# sboxs.net
KiCad netlist of a schematic drawn in EAGLE
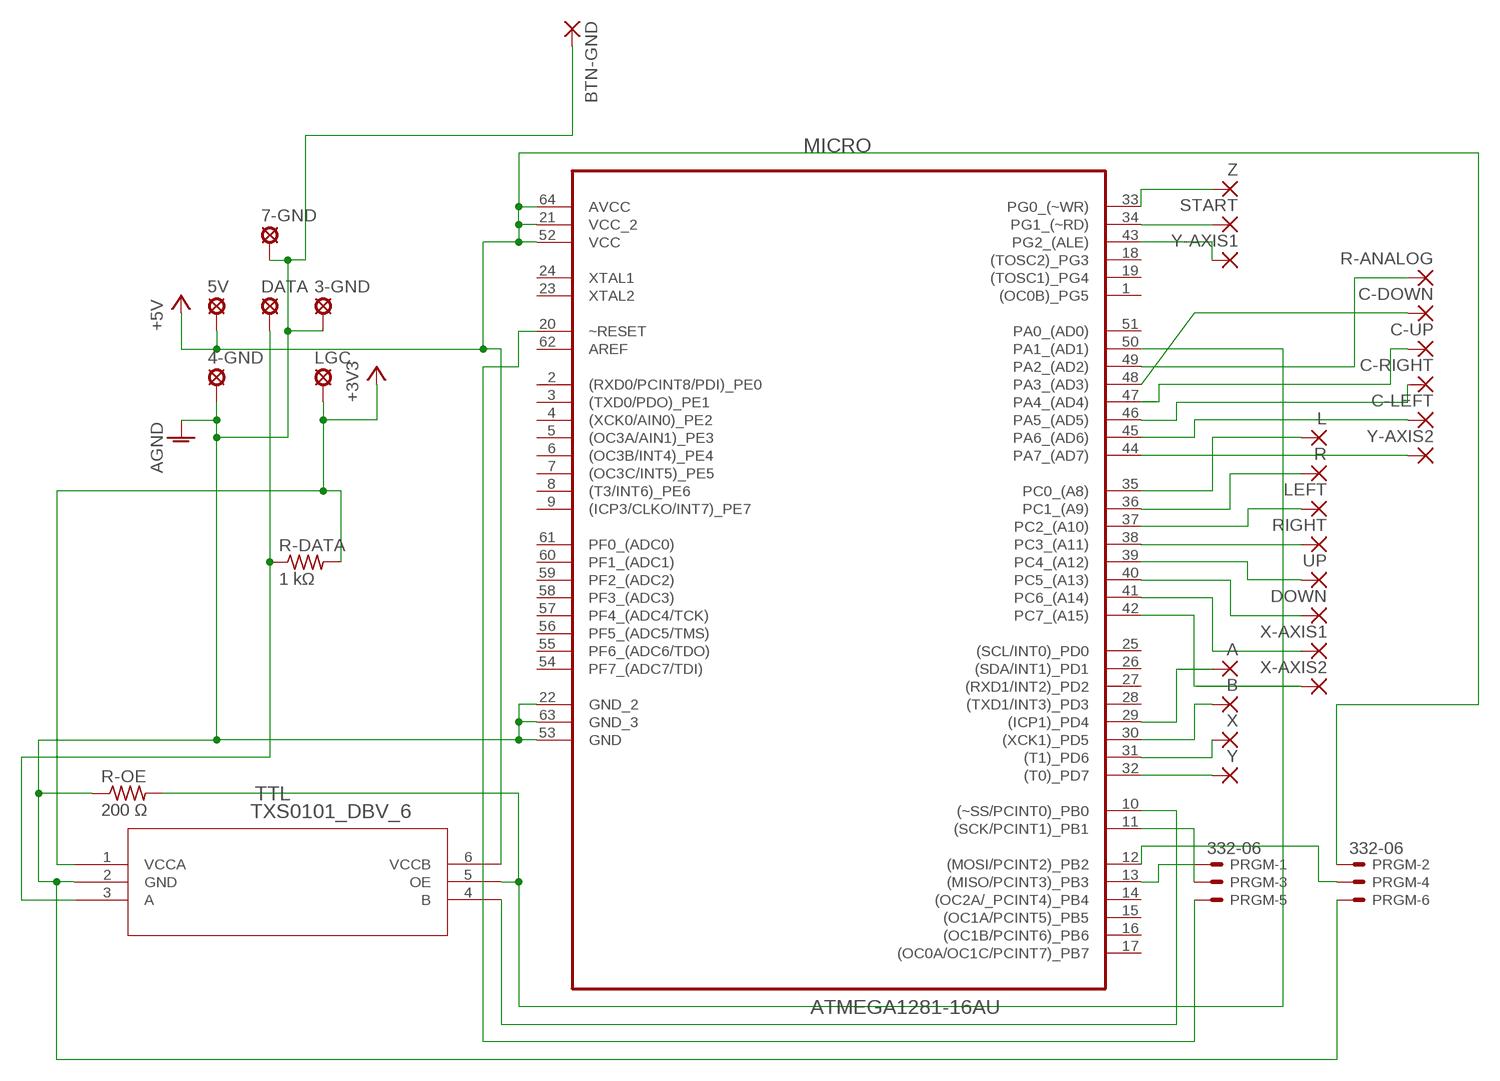
[diagram p0: schematic, sheet 1]

(export (version "E")
  (design (tool "Eeschema 10.0.6"))
  (components
    (comp (ref "3-GND")
      (value "LSP10")
      (footprint "eagle-import:LSP10")
      (libsource (lib "eagle-import") (part "LSP10"))
    )
    (comp (ref "4-GND")
      (value "LSP10")
      (footprint "eagle-import:LSP10")
      (libsource (lib "eagle-import") (part "LSP10"))
    )
    (comp (ref "5V")
      (value "LSP10")
      (footprint "eagle-import:LSP10")
      (libsource (lib "eagle-import") (part "LSP10"))
    )
    (comp (ref "7-GND")
      (value "LSP10")
      (footprint "eagle-import:LSP10")
      (libsource (lib "eagle-import") (part "LSP10"))
    )
    (comp (ref "A")
      (value "1,6/0,8")
      (footprint "eagle-import:1,6_0,8")
      (libsource (lib "eagle-import") (part "1,6/0,8"))
    )
    (comp (ref "B")
      (value "1,6/0,8")
      (footprint "eagle-import:1,6_0,8")
      (libsource (lib "eagle-import") (part "1,6/0,8"))
    )
    (comp (ref "BTN-GND")
      (value "1,6/0,8")
      (footprint "eagle-import:1,6_0,8")
      (libsource (lib "eagle-import") (part "1,6/0,8"))
    )
    (comp (ref "C-DOWN")
      (value "1,6/0,8")
      (footprint "eagle-import:1,6_0,8")
      (libsource (lib "eagle-import") (part "1,6/0,8"))
    )
    (comp (ref "C-LEFT")
      (value "1,6/0,8")
      (footprint "eagle-import:1,6_0,8")
      (libsource (lib "eagle-import") (part "1,6/0,8"))
    )
    (comp (ref "C-RIGHT")
      (value "1,6/0,8")
      (footprint "eagle-import:1,6_0,8")
      (libsource (lib "eagle-import") (part "1,6/0,8"))
    )
    (comp (ref "C-UP")
      (value "1,6/0,8")
      (footprint "eagle-import:1,6_0,8")
      (libsource (lib "eagle-import") (part "1,6/0,8"))
    )
    (comp (ref "DATA")
      (value "LSP10")
      (footprint "eagle-import:LSP10")
      (libsource (lib "eagle-import") (part "LSP10"))
    )
    (comp (ref "DOWN")
      (value "1,6/0,8")
      (footprint "eagle-import:1,6_0,8")
      (libsource (lib "eagle-import") (part "1,6/0,8"))
    )
    (comp (ref "L")
      (value "1,6/0,8")
      (footprint "eagle-import:1,6_0,8")
      (libsource (lib "eagle-import") (part "1,6/0,8"))
    )
    (comp (ref "LEFT")
      (value "1,6/0,8")
      (footprint "eagle-import:1,6_0,8")
      (libsource (lib "eagle-import") (part "1,6/0,8"))
    )
    (comp (ref "LGC")
      (value "LSP10")
      (footprint "eagle-import:LSP10")
      (libsource (lib "eagle-import") (part "LSP10"))
    )
    (comp (ref "MICRO")
      (value "ATMEGA1281-16AU")
      (footprint "eagle-import:QFP80P1600X1600X120-64N")
      (libsource (lib "eagle-import") (part "ATMEGA1281-16AU"))
    )
    (comp (ref "PRGM")
      (value "332-06")
      (footprint "eagle-import:332-06")
      (libsource (lib "eagle-import") (part "332-06"))
    )
    (comp (ref "R")
      (value "1,6/0,8")
      (footprint "eagle-import:1,6_0,8")
      (libsource (lib "eagle-import") (part "1,6/0,8"))
    )
    (comp (ref "R-ANALOG")
      (value "1,6/0,8")
      (footprint "eagle-import:1,6_0,8")
      (libsource (lib "eagle-import") (part "1,6/0,8"))
    )
    (comp (ref "R-DATA")
      (value "1 kΩ")
      (footprint "eagle-import:0207_12")
      (libsource (lib "eagle-import") (part "R-US_0207/12"))
    )
    (comp (ref "R-OE")
      (value "200 Ω")
      (footprint "eagle-import:0207_12")
      (libsource (lib "eagle-import") (part "R-US_0207/12"))
    )
    (comp (ref "RIGHT")
      (value "1,6/0,8")
      (footprint "eagle-import:1,6_0,8")
      (libsource (lib "eagle-import") (part "1,6/0,8"))
    )
    (comp (ref "START")
      (value "1,6/0,8")
      (footprint "eagle-import:1,6_0,8")
      (libsource (lib "eagle-import") (part "1,6/0,8"))
    )
    (comp (ref "TTL")
      (value "TXS0101_DBV_6")
      (footprint "eagle-import:DBV6")
      (fields
        (field (name "GENERIC_PART_NUMBER") "TXS0101")
        (field (name "MANUFACTURER") "Texas Instruments")
        (field (name "MANUFACTURER_PART_NUMBER") "txs0101_dbv_6")
      )
      (libsource (lib "eagle-import") (part "TXS0101_DBV_6"))
    )
    (comp (ref "UP")
      (value "1,6/0,8")
      (footprint "eagle-import:1,6_0,8")
      (libsource (lib "eagle-import") (part "1,6/0,8"))
    )
    (comp (ref "X")
      (value "1,6/0,8")
      (footprint "eagle-import:1,6_0,8")
      (libsource (lib "eagle-import") (part "1,6/0,8"))
    )
    (comp (ref "X-AXIS1")
      (value "1,6/0,8")
      (footprint "eagle-import:1,6_0,8")
      (libsource (lib "eagle-import") (part "1,6/0,8"))
    )
    (comp (ref "X-AXIS2")
      (value "1,6/0,8")
      (footprint "eagle-import:1,6_0,8")
      (libsource (lib "eagle-import") (part "1,6/0,8"))
    )
    (comp (ref "Y")
      (value "1,6/0,8")
      (footprint "eagle-import:1,6_0,8")
      (libsource (lib "eagle-import") (part "1,6/0,8"))
    )
    (comp (ref "Y-AXIS1")
      (value "1,6/0,8")
      (footprint "eagle-import:1,6_0,8")
      (libsource (lib "eagle-import") (part "1,6/0,8"))
    )
    (comp (ref "Y-AXIS2")
      (value "1,6/0,8")
      (footprint "eagle-import:1,6_0,8")
      (libsource (lib "eagle-import") (part "1,6/0,8"))
    )
    (comp (ref "Z")
      (value "1,6/0,8")
      (footprint "eagle-import:1,6_0,8")
      (libsource (lib "eagle-import") (part "1,6/0,8"))
    )
  )
  (nets
    (net (code "1") (name "+3V3") (class "Default")
      (node (ref "LGC") (pin "MP") (pinfunction "MP_MP") (pintype "passive"))
      (node (ref "R-DATA") (pin "2") (pinfunction "2_2") (pintype "passive"))
      (node (ref "TTL") (pin "1") (pinfunction "VCCA_1") (pintype "power_in"))
    )
    (net (code "2") (name "+5V") (class "Default")
      (node (ref "5V") (pin "MP") (pinfunction "MP_MP") (pintype "passive"))
      (node (ref "MICRO") (pin "21") (pinfunction "VCC_2_21") (pintype "power_in"))
      (node (ref "MICRO") (pin "52") (pinfunction "VCC_52") (pintype "power_in"))
      (node (ref "MICRO") (pin "64") (pinfunction "AVCC_64") (pintype "power_in"))
      (node (ref "PRGM") (pin "2") (pinfunction "S_2") (pintype "passive"))
      (node (ref "TTL") (pin "6") (pinfunction "VCCB_6") (pintype "power_in"))
    )
    (net (code "3") (name "AGND") (class "Default")
      (node (ref "3-GND") (pin "MP") (pinfunction "MP_MP") (pintype "passive"))
      (node (ref "4-GND") (pin "MP") (pinfunction "MP_MP") (pintype "passive"))
      (node (ref "7-GND") (pin "MP") (pinfunction "MP_MP") (pintype "passive"))
      (node (ref "BTN-GND") (pin "1") (pinfunction "P_1") (pintype "passive"))
      (node (ref "MICRO") (pin "22") (pinfunction "GND_2_22") (pintype "passive"))
      (node (ref "MICRO") (pin "53") (pinfunction "GND_53") (pintype "passive"))
      (node (ref "MICRO") (pin "63") (pinfunction "GND_3_63") (pintype "passive"))
      (node (ref "PRGM") (pin "6") (pinfunction "S_6") (pintype "passive"))
      (node (ref "R-OE") (pin "1") (pinfunction "1_1") (pintype "passive"))
      (node (ref "TTL") (pin "2") (pinfunction "GND_2") (pintype "power_in"))
    )
    (net (code "4") (name "Net-(A-P)") (class "Default")
      (node (ref "A") (pin "1") (pinfunction "P_1") (pintype "passive"))
      (node (ref "MICRO") (pin "29") (pinfunction "(ICP1)_PD4_29") (pintype "bidirectional"))
    )
    (net (code "5") (name "Net-(B-P)") (class "Default")
      (node (ref "B") (pin "1") (pinfunction "P_1") (pintype "passive"))
      (node (ref "MICRO") (pin "30") (pinfunction "(XCK1)_PD5_30") (pintype "bidirectional"))
    )
    (net (code "6") (name "Net-(C-DOWN-P)") (class "Default")
      (node (ref "C-DOWN") (pin "1") (pinfunction "P_1") (pintype "passive"))
      (node (ref "MICRO") (pin "48") (pinfunction "PA3_(AD3)_48") (pintype "bidirectional"))
    )
    (net (code "7") (name "Net-(C-LEFT-P)") (class "Default")
      (node (ref "C-LEFT") (pin "1") (pinfunction "P_1") (pintype "passive"))
      (node (ref "MICRO") (pin "45") (pinfunction "PA6_(AD6)_45") (pintype "bidirectional"))
    )
    (net (code "8") (name "Net-(C-RIGHT-P)") (class "Default")
      (node (ref "C-RIGHT") (pin "1") (pinfunction "P_1") (pintype "passive"))
      (node (ref "MICRO") (pin "46") (pinfunction "PA5_(AD5)_46") (pintype "bidirectional"))
    )
    (net (code "9") (name "Net-(C-UP-P)") (class "Default")
      (node (ref "C-UP") (pin "1") (pinfunction "P_1") (pintype "passive"))
      (node (ref "MICRO") (pin "47") (pinfunction "PA4_(AD4)_47") (pintype "bidirectional"))
    )
    (net (code "10") (name "Net-(DOWN-P)") (class "Default")
      (node (ref "DOWN") (pin "1") (pinfunction "P_1") (pintype "passive"))
      (node (ref "MICRO") (pin "40") (pinfunction "PC5_(A13)_40") (pintype "bidirectional"))
    )
    (net (code "11") (name "Net-(L-P)") (class "Default")
      (node (ref "L") (pin "1") (pinfunction "P_1") (pintype "passive"))
      (node (ref "MICRO") (pin "35") (pinfunction "PC0_(A8)_35") (pintype "bidirectional"))
    )
    (net (code "12") (name "Net-(LEFT-P)") (class "Default")
      (node (ref "LEFT") (pin "1") (pinfunction "P_1") (pintype "passive"))
      (node (ref "MICRO") (pin "37") (pinfunction "PC2_(A10)_37") (pintype "bidirectional"))
    )
    (net (code "13") (name "Net-(MICRO-(MISO{slash}PCINT3)_PB3)") (class "Default")
      (node (ref "MICRO") (pin "13") (pinfunction "(MISO/PCINT3)_PB3_13") (pintype "bidirectional"))
      (node (ref "PRGM") (pin "1") (pinfunction "S_1") (pintype "passive"))
    )
    (net (code "14") (name "Net-(MICRO-(MOSI{slash}PCINT2)_PB2)") (class "Default")
      (node (ref "MICRO") (pin "12") (pinfunction "(MOSI/PCINT2)_PB2_12") (pintype "bidirectional"))
      (node (ref "PRGM") (pin "4") (pinfunction "S_4") (pintype "passive"))
    )
    (net (code "15") (name "Net-(MICRO-(SCK{slash}PCINT1)_PB1)") (class "Default")
      (node (ref "MICRO") (pin "11") (pinfunction "(SCK/PCINT1)_PB1_11") (pintype "bidirectional"))
      (node (ref "PRGM") (pin "3") (pinfunction "S_3") (pintype "passive"))
    )
    (net (code "16") (name "Net-(MICRO-(T0)_PD7)") (class "Default")
      (node (ref "MICRO") (pin "32") (pinfunction "(T0)_PD7_32") (pintype "bidirectional"))
      (node (ref "Y") (pin "1") (pinfunction "P_1") (pintype "passive"))
    )
    (net (code "17") (name "Net-(MICRO-(T1)_PD6)") (class "Default")
      (node (ref "MICRO") (pin "31") (pinfunction "(T1)_PD6_31") (pintype "bidirectional"))
      (node (ref "X") (pin "1") (pinfunction "P_1") (pintype "passive"))
    )
    (net (code "18") (name "Net-(MICRO-(~{SS{slash}PCINT0})_PB0)") (class "Default")
      (node (ref "MICRO") (pin "10") (pinfunction "(~{SS/PCINT0})_PB0_10") (pintype "bidirectional"))
      (node (ref "TTL") (pin "4") (pinfunction "B_4") (pintype "bidirectional"))
    )
    (net (code "19") (name "Net-(MICRO-PA1_(AD1))") (class "Default")
      (node (ref "MICRO") (pin "50") (pinfunction "PA1_(AD1)_50") (pintype "bidirectional"))
      (node (ref "R-OE") (pin "2") (pinfunction "2_2") (pintype "passive"))
      (node (ref "TTL") (pin "5") (pinfunction "OE_5") (pintype "output"))
    )
    (net (code "20") (name "Net-(MICRO-PA2_(AD2))") (class "Default")
      (node (ref "MICRO") (pin "49") (pinfunction "PA2_(AD2)_49") (pintype "bidirectional"))
      (node (ref "R-ANALOG") (pin "1") (pinfunction "P_1") (pintype "passive"))
    )
    (net (code "21") (name "Net-(MICRO-PA7_(AD7))") (class "Default")
      (node (ref "MICRO") (pin "44") (pinfunction "PA7_(AD7)_44") (pintype "bidirectional"))
      (node (ref "Y-AXIS2") (pin "1") (pinfunction "P_1") (pintype "passive"))
    )
    (net (code "22") (name "Net-(MICRO-PC1_(A9))") (class "Default")
      (node (ref "MICRO") (pin "36") (pinfunction "PC1_(A9)_36") (pintype "bidirectional"))
      (node (ref "R") (pin "1") (pinfunction "P_1") (pintype "passive"))
    )
    (net (code "23") (name "Net-(MICRO-PC3_(A11))") (class "Default")
      (node (ref "MICRO") (pin "38") (pinfunction "PC3_(A11)_38") (pintype "bidirectional"))
      (node (ref "RIGHT") (pin "1") (pinfunction "P_1") (pintype "passive"))
    )
    (net (code "24") (name "Net-(MICRO-PC4_(A12))") (class "Default")
      (node (ref "MICRO") (pin "39") (pinfunction "PC4_(A12)_39") (pintype "bidirectional"))
      (node (ref "UP") (pin "1") (pinfunction "P_1") (pintype "passive"))
    )
    (net (code "25") (name "Net-(MICRO-PC6_(A14))") (class "Default")
      (node (ref "MICRO") (pin "41") (pinfunction "PC6_(A14)_41") (pintype "bidirectional"))
      (node (ref "X-AXIS1") (pin "1") (pinfunction "P_1") (pintype "passive"))
    )
    (net (code "26") (name "Net-(MICRO-PC7_(A15))") (class "Default")
      (node (ref "MICRO") (pin "42") (pinfunction "PC7_(A15)_42") (pintype "bidirectional"))
      (node (ref "X-AXIS2") (pin "1") (pinfunction "P_1") (pintype "passive"))
    )
    (net (code "27") (name "Net-(MICRO-PG0_(~{WR}))") (class "Default")
      (node (ref "MICRO") (pin "33") (pinfunction "PG0_(~{WR})_33") (pintype "bidirectional"))
      (node (ref "Z") (pin "1") (pinfunction "P_1") (pintype "passive"))
    )
    (net (code "28") (name "Net-(MICRO-PG1_(~{RD}))") (class "Default")
      (node (ref "MICRO") (pin "34") (pinfunction "PG1_(~{RD})_34") (pintype "bidirectional"))
      (node (ref "START") (pin "1") (pinfunction "P_1") (pintype "passive"))
    )
    (net (code "29") (name "Net-(MICRO-PG2_(ALE))") (class "Default")
      (node (ref "MICRO") (pin "43") (pinfunction "PG2_(ALE)_43") (pintype "bidirectional"))
      (node (ref "Y-AXIS1") (pin "1") (pinfunction "P_1") (pintype "passive"))
    )
    (net (code "30") (name "Net-(MICRO-~{RESET})") (class "Default")
      (node (ref "MICRO") (pin "20") (pinfunction "~{RESET}_20") (pintype "input"))
      (node (ref "PRGM") (pin "5") (pinfunction "S_5") (pintype "passive"))
    )
    (net (code "31") (name "Net-(TTL-A)") (class "Default")
      (node (ref "DATA") (pin "MP") (pinfunction "MP_MP") (pintype "passive"))
      (node (ref "R-DATA") (pin "1") (pinfunction "1_1") (pintype "passive"))
      (node (ref "TTL") (pin "3") (pinfunction "A_3") (pintype "bidirectional"))
    )
    (net (code "32") (name "unconnected-(MICRO-(ICP3{slash}CLKO{slash}INT7)_PE7-Pad9)") (class "Default")
      (node (ref "MICRO") (pin "9") (pinfunction "(ICP3/CLKO/INT7)_PE7_9") (pintype "bidirectional"))
    )
    (net (code "33") (name "unconnected-(MICRO-(OC0A{slash}OC1C{slash}PCINT7)_PB7-Pad17)") (class "Default")
      (node (ref "MICRO") (pin "17") (pinfunction "(OC0A/OC1C/PCINT7)_PB7_17") (pintype "bidirectional"))
    )
    (net (code "34") (name "unconnected-(MICRO-(OC0B)_PG5-Pad1)") (class "Default")
      (node (ref "MICRO") (pin "1") (pinfunction "(OC0B)_PG5_1") (pintype "bidirectional"))
    )
    (net (code "35") (name "unconnected-(MICRO-(OC1A{slash}PCINT5)_PB5-Pad15)") (class "Default")
      (node (ref "MICRO") (pin "15") (pinfunction "(OC1A/PCINT5)_PB5_15") (pintype "bidirectional"))
    )
    (net (code "36") (name "unconnected-(MICRO-(OC1B{slash}PCINT6)_PB6-Pad16)") (class "Default")
      (node (ref "MICRO") (pin "16") (pinfunction "(OC1B/PCINT6)_PB6_16") (pintype "bidirectional"))
    )
    (net (code "37") (name "unconnected-(MICRO-(OC2A{slash}_PCINT4)_PB4-Pad14)") (class "Default")
      (node (ref "MICRO") (pin "14") (pinfunction "(OC2A/_PCINT4)_PB4_14") (pintype "bidirectional"))
    )
    (net (code "38") (name "unconnected-(MICRO-(OC3A{slash}AIN1)_PE3-Pad5)") (class "Default")
      (node (ref "MICRO") (pin "5") (pinfunction "(OC3A/AIN1)_PE3_5") (pintype "bidirectional"))
    )
    (net (code "39") (name "unconnected-(MICRO-(OC3B{slash}INT4)_PE4-Pad6)") (class "Default")
      (node (ref "MICRO") (pin "6") (pinfunction "(OC3B/INT4)_PE4_6") (pintype "bidirectional"))
    )
    (net (code "40") (name "unconnected-(MICRO-(OC3C{slash}INT5)_PE5-Pad7)") (class "Default")
      (node (ref "MICRO") (pin "7") (pinfunction "(OC3C/INT5)_PE5_7") (pintype "bidirectional"))
    )
    (net (code "41") (name "unconnected-(MICRO-(RXD0{slash}PCINT8{slash}PDI)_PE0-Pad2)") (class "Default")
      (node (ref "MICRO") (pin "2") (pinfunction "(RXD0/PCINT8/PDI)_PE0_2") (pintype "bidirectional"))
    )
    (net (code "42") (name "unconnected-(MICRO-(RXD1{slash}INT2)_PD2-Pad27)") (class "Default")
      (node (ref "MICRO") (pin "27") (pinfunction "(RXD1/INT2)_PD2_27") (pintype "bidirectional"))
    )
    (net (code "43") (name "unconnected-(MICRO-(SCL{slash}INT0)_PD0-Pad25)") (class "Default")
      (node (ref "MICRO") (pin "25") (pinfunction "(SCL/INT0)_PD0_25") (pintype "bidirectional"))
    )
    (net (code "44") (name "unconnected-(MICRO-(SDA{slash}INT1)_PD1-Pad26)") (class "Default")
      (node (ref "MICRO") (pin "26") (pinfunction "(SDA/INT1)_PD1_26") (pintype "bidirectional"))
    )
    (net (code "45") (name "unconnected-(MICRO-(T3{slash}INT6)_PE6-Pad8)") (class "Default")
      (node (ref "MICRO") (pin "8") (pinfunction "(T3/INT6)_PE6_8") (pintype "bidirectional"))
    )
    (net (code "46") (name "unconnected-(MICRO-(TOSC1)_PG4-Pad19)") (class "Default")
      (node (ref "MICRO") (pin "19") (pinfunction "(TOSC1)_PG4_19") (pintype "bidirectional"))
    )
    (net (code "47") (name "unconnected-(MICRO-(TOSC2)_PG3-Pad18)") (class "Default")
      (node (ref "MICRO") (pin "18") (pinfunction "(TOSC2)_PG3_18") (pintype "bidirectional"))
    )
    (net (code "48") (name "unconnected-(MICRO-(TXD0{slash}PDO)_PE1-Pad3)") (class "Default")
      (node (ref "MICRO") (pin "3") (pinfunction "(TXD0/PDO)_PE1_3") (pintype "bidirectional"))
    )
    (net (code "49") (name "unconnected-(MICRO-(TXD1{slash}INT3)_PD3-Pad28)") (class "Default")
      (node (ref "MICRO") (pin "28") (pinfunction "(TXD1/INT3)_PD3_28") (pintype "bidirectional"))
    )
    (net (code "50") (name "unconnected-(MICRO-(XCK0{slash}AIN0)_PE2-Pad4)") (class "Default")
      (node (ref "MICRO") (pin "4") (pinfunction "(XCK0/AIN0)_PE2_4") (pintype "bidirectional"))
    )
    (net (code "51") (name "unconnected-(MICRO-AREF-Pad62)") (class "Default")
      (node (ref "MICRO") (pin "62") (pinfunction "AREF_62") (pintype "input"))
    )
    (net (code "52") (name "unconnected-(MICRO-PA0_(AD0)-Pad51)") (class "Default")
      (node (ref "MICRO") (pin "51") (pinfunction "PA0_(AD0)_51") (pintype "bidirectional"))
    )
    (net (code "53") (name "unconnected-(MICRO-PF0_(ADC0)-Pad61)") (class "Default")
      (node (ref "MICRO") (pin "61") (pinfunction "PF0_(ADC0)_61") (pintype "bidirectional"))
    )
    (net (code "54") (name "unconnected-(MICRO-PF1_(ADC1)-Pad60)") (class "Default")
      (node (ref "MICRO") (pin "60") (pinfunction "PF1_(ADC1)_60") (pintype "bidirectional"))
    )
    (net (code "55") (name "unconnected-(MICRO-PF2_(ADC2)-Pad59)") (class "Default")
      (node (ref "MICRO") (pin "59") (pinfunction "PF2_(ADC2)_59") (pintype "bidirectional"))
    )
    (net (code "56") (name "unconnected-(MICRO-PF3_(ADC3)-Pad58)") (class "Default")
      (node (ref "MICRO") (pin "58") (pinfunction "PF3_(ADC3)_58") (pintype "bidirectional"))
    )
    (net (code "57") (name "unconnected-(MICRO-PF4_(ADC4{slash}TCK)-Pad57)") (class "Default")
      (node (ref "MICRO") (pin "57") (pinfunction "PF4_(ADC4/TCK)_57") (pintype "bidirectional"))
    )
    (net (code "58") (name "unconnected-(MICRO-PF5_(ADC5{slash}TMS)-Pad56)") (class "Default")
      (node (ref "MICRO") (pin "56") (pinfunction "PF5_(ADC5/TMS)_56") (pintype "bidirectional"))
    )
    (net (code "59") (name "unconnected-(MICRO-PF6_(ADC6{slash}TDO)-Pad55)") (class "Default")
      (node (ref "MICRO") (pin "55") (pinfunction "PF6_(ADC6/TDO)_55") (pintype "bidirectional"))
    )
    (net (code "60") (name "unconnected-(MICRO-PF7_(ADC7{slash}TDI)-Pad54)") (class "Default")
      (node (ref "MICRO") (pin "54") (pinfunction "PF7_(ADC7/TDI)_54") (pintype "bidirectional"))
    )
    (net (code "61") (name "unconnected-(MICRO-XTAL1-Pad24)") (class "Default")
      (node (ref "MICRO") (pin "24") (pinfunction "XTAL1_24") (pintype "input"))
    )
    (net (code "62") (name "unconnected-(MICRO-XTAL2-Pad23)") (class "Default")
      (node (ref "MICRO") (pin "23") (pinfunction "XTAL2_23") (pintype "input"))
    )
  )
)
